# LedDriver.net
KiCad netlist of a schematic drawn in EAGLE
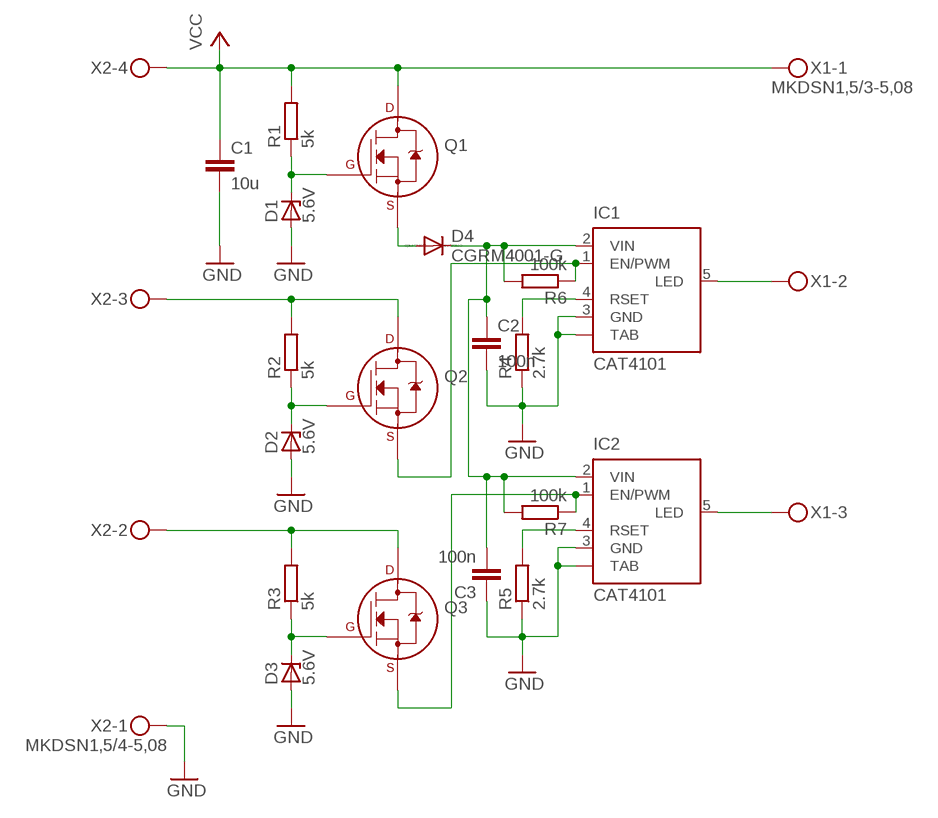
[diagram p0: schematic, sheet 1]

(export (version "E")
  (design (tool "Eeschema 10.0.6"))
  (components
    (comp (ref "C1")
      (value "10u")
      (footprint "eagle-import:C1210")
      (libsource (lib "eagle-import") (part "C-EUC1210"))
    )
    (comp (ref "C2")
      (value "100n")
      (footprint "eagle-import:C0402")
      (libsource (lib "eagle-import") (part "C-EUC0402"))
    )
    (comp (ref "C3")
      (value "100n")
      (footprint "eagle-import:C0402")
      (libsource (lib "eagle-import") (part "C-EUC0402"))
    )
    (comp (ref "D1")
      (value "5.6V")
      (footprint "eagle-import:SOD80C")
      (libsource (lib "eagle-import") (part "ZENER-DIODESOD80C"))
    )
    (comp (ref "D2")
      (value "5.6V")
      (footprint "eagle-import:SOD80C")
      (libsource (lib "eagle-import") (part "ZENER-DIODESOD80C"))
    )
    (comp (ref "D3")
      (value "5.6V")
      (footprint "eagle-import:SOD80C")
      (libsource (lib "eagle-import") (part "ZENER-DIODESOD80C"))
    )
    (comp (ref "D4")
      (value "CGRM4001-G")
      (footprint "eagle-import:SOD-123_MINI-SMA")
      (libsource (lib "eagle-import") (part "CGRM400-G1"))
    )
    (comp (ref "IC1")
      (value "CAT4101")
      (footprint "eagle-import:TO263_5")
      (fields (field (name "MPN") "CAT4101TV-T75"))
      (libsource (lib "eagle-import") (part "CAT4101"))
    )
    (comp (ref "IC2")
      (value "CAT4101")
      (footprint "eagle-import:TO263_5")
      (fields (field (name "MPN") "CAT4101TV-T75"))
      (libsource (lib "eagle-import") (part "CAT4101"))
    )
    (comp (ref "Q1")
      (value "2N7002_SOT23")
      (footprint "eagle-import:SOT-23")
      (libsource (lib "eagle-import") (part "2N700_SOT232"))
    )
    (comp (ref "Q2")
      (value "2N7002_SOT23")
      (footprint "eagle-import:SOT-23")
      (libsource (lib "eagle-import") (part "2N700_SOT232"))
    )
    (comp (ref "Q3")
      (value "2N7002_SOT23")
      (footprint "eagle-import:SOT-23")
      (libsource (lib "eagle-import") (part "2N700_SOT232"))
    )
    (comp (ref "R1")
      (value "5k")
      (footprint "eagle-import:R0603")
      (libsource (lib "eagle-import") (part "R-EU_R0603"))
    )
    (comp (ref "R2")
      (value "5k")
      (footprint "eagle-import:R0603")
      (libsource (lib "eagle-import") (part "R-EU_R0603"))
    )
    (comp (ref "R3")
      (value "5k")
      (footprint "eagle-import:R0603")
      (libsource (lib "eagle-import") (part "R-EU_R0603"))
    )
    (comp (ref "R4")
      (value "2.7k")
      (footprint "eagle-import:R0603")
      (libsource (lib "eagle-import") (part "R-EU_R0603"))
    )
    (comp (ref "R5")
      (value "2.7k")
      (footprint "eagle-import:R0603")
      (libsource (lib "eagle-import") (part "R-EU_R0603"))
    )
    (comp (ref "R6")
      (value "100k")
      (footprint "eagle-import:R0603")
      (libsource (lib "eagle-import") (part "R-EU_R0603"))
    )
    (comp (ref "R7")
      (value "100k")
      (footprint "eagle-import:R0603")
      (libsource (lib "eagle-import") (part "R-EU_R0603"))
    )
    (comp (ref "X1")
      (value "MKDSN1,5/3-5,08")
      (footprint "eagle-import:MKDSN1,5_3-5,08")
      (fields (field (name "MPN") "SMKDSN1,5/3-5,08"))
      (libsource (lib "eagle-import") (part "MKDSN1,5/3-5,08"))
    )
    (comp (ref "X2")
      (value "MKDSN1,5/4-5,08")
      (footprint "eagle-import:MKDSN1,5_4-5,08")
      (fields (field (name "MPN") "SMKDSN1,5/4-5,08"))
      (libsource (lib "eagle-import") (part "MKDSN1,5/4-5,08"))
    )
  )
  (nets
    (net (code "1") (name "GND") (class "Default")
      (node (ref "C1") (pin "2") (pinfunction "2_2") (pintype "passive"))
      (node (ref "C2") (pin "2") (pinfunction "2_2") (pintype "passive"))
      (node (ref "C3") (pin "1") (pinfunction "1_1") (pintype "passive"))
      (node (ref "D1") (pin "A") (pinfunction "A_A") (pintype "passive"))
      (node (ref "D2") (pin "A") (pinfunction "A_A") (pintype "passive"))
      (node (ref "D3") (pin "A") (pinfunction "A_A") (pintype "passive"))
      (node (ref "IC1") (pin "3") (pinfunction "GND_3") (pintype "power_in"))
      (node (ref "IC1") (pin "TAB") (pinfunction "TAB_TAB") (pintype "passive"))
      (node (ref "IC2") (pin "3") (pinfunction "GND_3") (pintype "power_in"))
      (node (ref "IC2") (pin "TAB") (pinfunction "TAB_TAB") (pintype "passive"))
      (node (ref "R4") (pin "1") (pinfunction "1_1") (pintype "passive"))
      (node (ref "R5") (pin "1") (pinfunction "1_1") (pintype "passive"))
      (node (ref "X2") (pin "1") (pinfunction "KL_1") (pintype "passive"))
    )
    (net (code "2") (name "Net-(IC1-EN{slash}PWM)") (class "Default")
      (node (ref "IC1") (pin "1") (pinfunction "EN/PWM_1") (pintype "input"))
      (node (ref "Q2") (pin "2") (pinfunction "S_2") (pintype "bidirectional"))
      (node (ref "R6") (pin "1") (pinfunction "1_1") (pintype "passive"))
    )
    (net (code "3") (name "Net-(IC1-LED)") (class "Default")
      (node (ref "IC1") (pin "5") (pinfunction "LED_5") (pintype "power_in"))
      (node (ref "X1") (pin "2") (pinfunction "KL_2") (pintype "passive"))
    )
    (net (code "4") (name "Net-(IC1-RSET)") (class "Default")
      (node (ref "IC1") (pin "4") (pinfunction "RSET_4") (pintype "input"))
      (node (ref "R4") (pin "2") (pinfunction "2_2") (pintype "passive"))
    )
    (net (code "5") (name "Net-(IC1-VIN)") (class "Default")
      (node (ref "C2") (pin "1") (pinfunction "1_1") (pintype "passive"))
      (node (ref "C3") (pin "2") (pinfunction "2_2") (pintype "passive"))
      (node (ref "D4") (pin "C") (pinfunction "C_C") (pintype "passive"))
      (node (ref "IC1") (pin "2") (pinfunction "VIN_2") (pintype "input"))
      (node (ref "IC2") (pin "2") (pinfunction "VIN_2") (pintype "input"))
      (node (ref "R6") (pin "2") (pinfunction "2_2") (pintype "passive"))
      (node (ref "R7") (pin "2") (pinfunction "2_2") (pintype "passive"))
    )
    (net (code "6") (name "Net-(IC2-EN{slash}PWM)") (class "Default")
      (node (ref "IC2") (pin "1") (pinfunction "EN/PWM_1") (pintype "input"))
      (node (ref "Q3") (pin "2") (pinfunction "S_2") (pintype "bidirectional"))
      (node (ref "R7") (pin "1") (pinfunction "1_1") (pintype "passive"))
    )
    (net (code "7") (name "Net-(IC2-LED)") (class "Default")
      (node (ref "IC2") (pin "5") (pinfunction "LED_5") (pintype "power_in"))
      (node (ref "X1") (pin "3") (pinfunction "KL_3") (pintype "passive"))
    )
    (net (code "8") (name "Net-(IC2-RSET)") (class "Default")
      (node (ref "IC2") (pin "4") (pinfunction "RSET_4") (pintype "input"))
      (node (ref "R5") (pin "2") (pinfunction "2_2") (pintype "passive"))
    )
    (net (code "9") (name "Net-(Q1-G)") (class "Default")
      (node (ref "D1") (pin "C") (pinfunction "C_C") (pintype "passive"))
      (node (ref "Q1") (pin "1") (pinfunction "G_1") (pintype "tri_state"))
      (node (ref "R1") (pin "1") (pinfunction "1_1") (pintype "passive"))
    )
    (net (code "10") (name "Net-(Q1-S)") (class "Default")
      (node (ref "D4") (pin "A") (pinfunction "A_A") (pintype "passive"))
      (node (ref "Q1") (pin "2") (pinfunction "S_2") (pintype "bidirectional"))
    )
    (net (code "11") (name "Net-(Q2-D)") (class "Default")
      (node (ref "Q2") (pin "3") (pinfunction "D_3") (pintype "bidirectional"))
      (node (ref "R2") (pin "2") (pinfunction "2_2") (pintype "passive"))
      (node (ref "X2") (pin "3") (pinfunction "KL_3") (pintype "passive"))
    )
    (net (code "12") (name "Net-(Q2-G)") (class "Default")
      (node (ref "D2") (pin "C") (pinfunction "C_C") (pintype "passive"))
      (node (ref "Q2") (pin "1") (pinfunction "G_1") (pintype "tri_state"))
      (node (ref "R2") (pin "1") (pinfunction "1_1") (pintype "passive"))
    )
    (net (code "13") (name "Net-(Q3-D)") (class "Default")
      (node (ref "Q3") (pin "3") (pinfunction "D_3") (pintype "bidirectional"))
      (node (ref "R3") (pin "2") (pinfunction "2_2") (pintype "passive"))
      (node (ref "X2") (pin "2") (pinfunction "KL_2") (pintype "passive"))
    )
    (net (code "14") (name "Net-(Q3-G)") (class "Default")
      (node (ref "D3") (pin "C") (pinfunction "C_C") (pintype "passive"))
      (node (ref "Q3") (pin "1") (pinfunction "G_1") (pintype "tri_state"))
      (node (ref "R3") (pin "1") (pinfunction "1_1") (pintype "passive"))
    )
    (net (code "15") (name "VCC") (class "Default")
      (node (ref "C1") (pin "1") (pinfunction "1_1") (pintype "passive"))
      (node (ref "Q1") (pin "3") (pinfunction "D_3") (pintype "bidirectional"))
      (node (ref "R1") (pin "2") (pinfunction "2_2") (pintype "passive"))
      (node (ref "X1") (pin "1") (pinfunction "KL_1") (pintype "passive"))
      (node (ref "X2") (pin "4") (pinfunction "KL_4") (pintype "passive"))
    )
  )
)
